# MotorDriver.net
KiCad netlist of a schematic drawn in Altium Designer
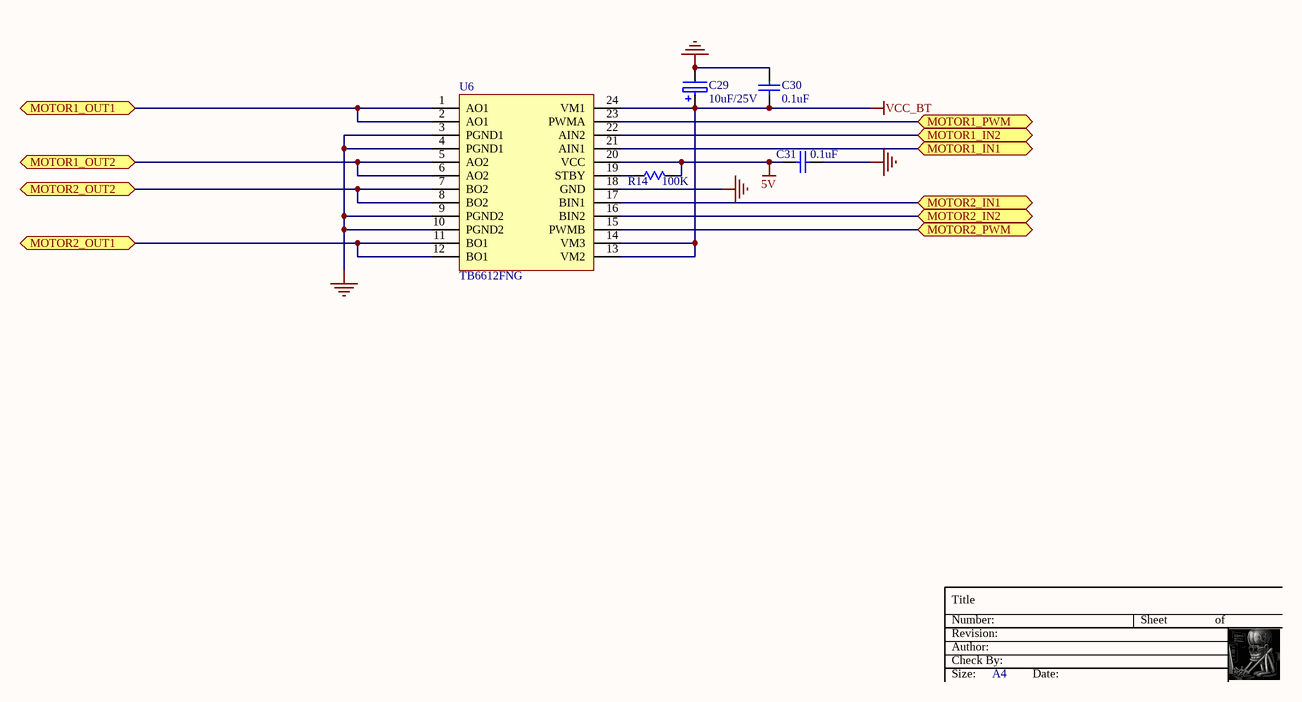
[diagram p0: MotorDriver.SchDoc]

(export (version "E")
  (design (tool "Eeschema 10.0.6"))
  (components
    (comp (ref "C29")
      (value "10uF/25V")
      (footprint "TC3528-1411")
      (description "Polarized Capacitor")
      (libsource (lib "Passive Components Class") (part "CAP-ELEC"))
    )
    (comp (ref "C30")
      (value "0.1uF")
      (footprint "C0603-S")
      (description "Capacitor")
      (libsource (lib "Passive Components Class") (part "CAP"))
    )
    (comp (ref "C31")
      (value "0.1uF")
      (footprint "C0603-S")
      (description "Capacitor")
      (libsource (lib "Passive Components Class") (part "CAP"))
    )
    (comp (ref "R14")
      (value "100K")
      (footprint "R0603-S")
      (description "Resistor")
      (libsource (lib "Passive Components Class") (part "RES"))
    )
    (comp (ref "U6")
      (value "TB6612FNG")
      (footprint "SSOP24-300-0.65A")
      (description "Driver IC for Dual DC motor")
      (libsource (lib "Driver Class") (part "TB6612FNG"))
    )
  )
  (nets
    (net (code "1") (name "/MOTOR1_IN1") (class "Default")
      (node (ref "U6") (pin "21") (pinfunction "AIN1_21") (pintype "passive"))
    )
    (net (code "2") (name "/MOTOR1_IN2") (class "Default")
      (node (ref "U6") (pin "22") (pinfunction "AIN2_22") (pintype "passive"))
    )
    (net (code "3") (name "/MOTOR1_OUT1") (class "Default")
      (node (ref "U6") (pin "1") (pinfunction "AO1_1") (pintype "passive"))
      (node (ref "U6") (pin "2") (pinfunction "AO1_2") (pintype "passive"))
    )
    (net (code "4") (name "/MOTOR1_OUT2") (class "Default")
      (node (ref "U6") (pin "5") (pinfunction "AO2_5") (pintype "passive"))
      (node (ref "U6") (pin "6") (pinfunction "AO2_6") (pintype "passive"))
    )
    (net (code "5") (name "/MOTOR1_PWM") (class "Default")
      (node (ref "U6") (pin "23") (pinfunction "PWMA_23") (pintype "passive"))
    )
    (net (code "6") (name "/MOTOR2_IN1") (class "Default")
      (node (ref "U6") (pin "17") (pinfunction "BIN1_17") (pintype "passive"))
    )
    (net (code "7") (name "/MOTOR2_IN2") (class "Default")
      (node (ref "U6") (pin "16") (pinfunction "BIN2_16") (pintype "passive"))
    )
    (net (code "8") (name "/MOTOR2_OUT1") (class "Default")
      (node (ref "U6") (pin "11") (pinfunction "BO1_11") (pintype "passive"))
      (node (ref "U6") (pin "12") (pinfunction "BO1_12") (pintype "passive"))
    )
    (net (code "9") (name "/MOTOR2_OUT2") (class "Default")
      (node (ref "U6") (pin "7") (pinfunction "BO2_7") (pintype "passive"))
      (node (ref "U6") (pin "8") (pinfunction "BO2_8") (pintype "passive"))
    )
    (net (code "10") (name "/MOTOR2_PWM") (class "Default")
      (node (ref "U6") (pin "15") (pinfunction "PWMB_15") (pintype "passive"))
    )
    (net (code "11") (name "5V") (class "Default")
      (node (ref "C31") (pin "2") (pinfunction "2_2") (pintype "passive"))
      (node (ref "R14") (pin "1") (pinfunction "1_1") (pintype "passive"))
      (node (ref "U6") (pin "20") (pinfunction "VCC_20") (pintype "passive"))
    )
    (net (code "12") (name "GND") (class "Default")
      (node (ref "C29") (pin "2") (pinfunction "2_2") (pintype "passive"))
      (node (ref "C30") (pin "2") (pinfunction "2_2") (pintype "passive"))
      (node (ref "C31") (pin "1") (pinfunction "1_1") (pintype "passive"))
      (node (ref "U6") (pin "10") (pinfunction "PGND2_10") (pintype "passive"))
      (node (ref "U6") (pin "18") (pinfunction "GND_18") (pintype "passive"))
      (node (ref "U6") (pin "3") (pinfunction "PGND1_3") (pintype "passive"))
      (node (ref "U6") (pin "4") (pinfunction "PGND1_4") (pintype "passive"))
      (node (ref "U6") (pin "9") (pinfunction "PGND2_9") (pintype "passive"))
    )
    (net (code "13") (name "Net-(U6-STBY)") (class "Default")
      (node (ref "R14") (pin "2") (pinfunction "2_2") (pintype "passive"))
      (node (ref "U6") (pin "19") (pinfunction "STBY_19") (pintype "passive"))
    )
    (net (code "14") (name "VCC_BT") (class "Default")
      (node (ref "C29") (pin "1") (pinfunction "1_1") (pintype "passive"))
      (node (ref "C30") (pin "1") (pinfunction "1_1") (pintype "passive"))
      (node (ref "U6") (pin "13") (pinfunction "VM2_13") (pintype "passive"))
      (node (ref "U6") (pin "14") (pinfunction "VM3_14") (pintype "passive"))
      (node (ref "U6") (pin "24") (pinfunction "VM1_24") (pintype "passive"))
    )
  )
)
